# MondoBrickbridge.net
KiCad netlist of a schematic drawn in EAGLE
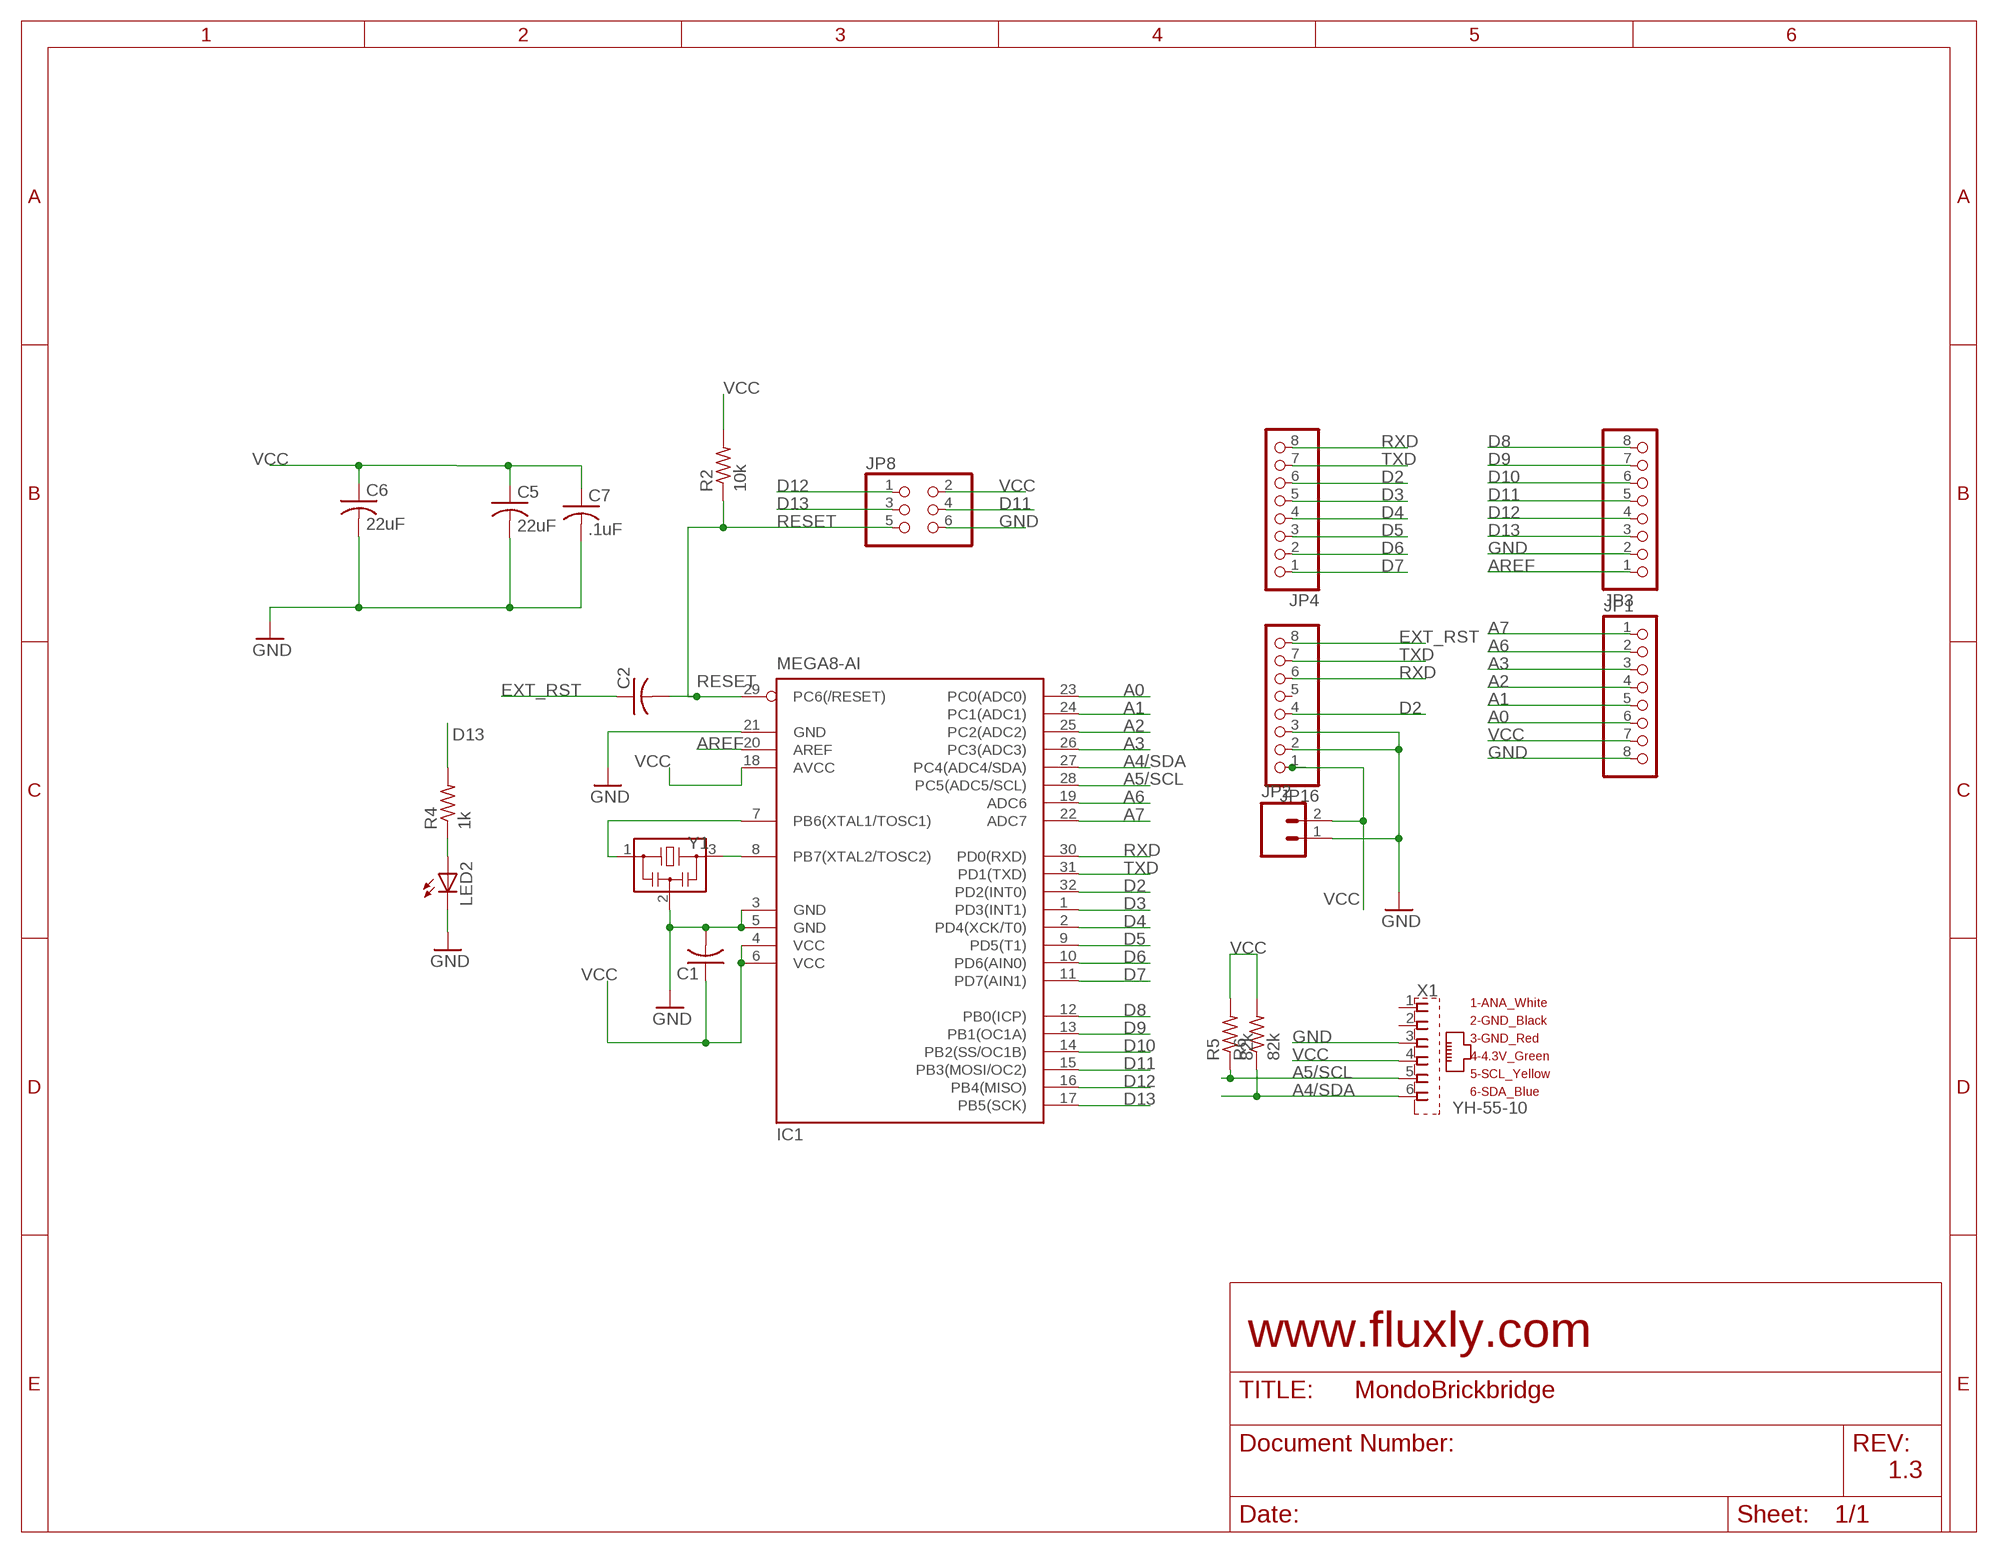
[diagram p0: schematic, sheet 1]

(export (version "E")
  (design (tool "Eeschema 10.0.6"))
  (components
    (comp (ref "C1")
      (value "C-USC0805K")
      (footprint "eagle-import:C0805K")
      (libsource (lib "eagle-import") (part "C-USC0805K"))
    )
    (comp (ref "C2")
      (value "C-USC0805K")
      (footprint "eagle-import:C0805K")
      (libsource (lib "eagle-import") (part "C-USC0805K"))
    )
    (comp (ref "C5")
      (value "22uF")
      (footprint "eagle-import:C1206K")
      (libsource (lib "eagle-import") (part "C-USC1206K"))
    )
    (comp (ref "C6")
      (value "22uF")
      (footprint "eagle-import:C1206K")
      (libsource (lib "eagle-import") (part "C-USC1206K"))
    )
    (comp (ref "C7")
      (value ".1uF")
      (footprint "eagle-import:C0805K")
      (libsource (lib "eagle-import") (part "C-USC0805K"))
    )
    (comp (ref "IC1")
      (value "MEGA8-AI")
      (footprint "eagle-import:TQFP32-08")
      (fields (field (name "MPN") "ATMEGA8-16AU"))
      (libsource (lib "eagle-import") (part "MEGA8-AI"))
    )
    (comp (ref "JP1")
      (value "PINHD-1X8BIG")
      (footprint "eagle-import:1X08-BIG")
      (libsource (lib "eagle-import") (part "PINHD-1X8BIG"))
    )
    (comp (ref "JP2")
      (value "M02PTH")
      (footprint "eagle-import:1X02")
      (libsource (lib "eagle-import") (part "M02PTH"))
    )
    (comp (ref "JP3")
      (value "PINHD-1X8BIG")
      (footprint "eagle-import:1X08-BIG")
      (libsource (lib "eagle-import") (part "PINHD-1X8BIG"))
    )
    (comp (ref "JP4")
      (value "PINHD-1X8BIG")
      (footprint "eagle-import:1X08-BIG")
      (libsource (lib "eagle-import") (part "PINHD-1X8BIG"))
    )
    (comp (ref "JP8")
      (value "PINHD-2X3")
      (footprint "eagle-import:2X03")
      (libsource (lib "eagle-import") (part "PINHD-2X3"))
    )
    (comp (ref "JP16")
      (value "PINHD-1X8BIG")
      (footprint "eagle-import:1X08-BIG")
      (libsource (lib "eagle-import") (part "PINHD-1X8BIG"))
    )
    (comp (ref "LED2")
      (value "LEDCHIPLED_1206")
      (footprint "eagle-import:CHIPLED_1206")
      (libsource (lib "eagle-import") (part "LEDCHIPLED_1206"))
    )
    (comp (ref "R2")
      (value "10k")
      (footprint "eagle-import:M0805")
      (libsource (lib "eagle-import") (part "R-US_M0805"))
    )
    (comp (ref "R4")
      (value "1k")
      (footprint "eagle-import:M0805")
      (libsource (lib "eagle-import") (part "R-US_M0805"))
    )
    (comp (ref "R5")
      (value "82k")
      (footprint "eagle-import:M0805")
      (libsource (lib "eagle-import") (part "R-US_M0805"))
    )
    (comp (ref "R6")
      (value "82k")
      (footprint "eagle-import:M0805")
      (libsource (lib "eagle-import") (part "R-US_M0805"))
    )
    (comp (ref "X1")
      (value "YH-55-10")
      (footprint "eagle-import:YH-55-10")
      (libsource (lib "eagle-import") (part "YH-55-10"))
    )
    (comp (ref "Y1")
      (value "RESONATOR")
      (footprint "eagle-import:EFOBM")
      (libsource (lib "eagle-import") (part "RESONATOR"))
    )
  )
  (nets
    (net (code "1") (name "/A0") (class "Default")
      (node (ref "IC1") (pin "23") (pinfunction "PC0(ADC0)_23") (pintype "bidirectional"))
      (node (ref "JP1") (pin "6") (pinfunction "6_6") (pintype "passive"))
    )
    (net (code "2") (name "/A1") (class "Default")
      (node (ref "IC1") (pin "24") (pinfunction "PC1(ADC1)_24") (pintype "bidirectional"))
      (node (ref "JP1") (pin "5") (pinfunction "5_5") (pintype "passive"))
    )
    (net (code "3") (name "/A2") (class "Default")
      (node (ref "IC1") (pin "25") (pinfunction "PC2(ADC2)_25") (pintype "bidirectional"))
      (node (ref "JP1") (pin "4") (pinfunction "4_4") (pintype "passive"))
    )
    (net (code "4") (name "/A3") (class "Default")
      (node (ref "IC1") (pin "26") (pinfunction "PC3(ADC3)_26") (pintype "bidirectional"))
      (node (ref "JP1") (pin "3") (pinfunction "3_3") (pintype "passive"))
    )
    (net (code "5") (name "/A4{slash}SDA") (class "Default")
      (node (ref "IC1") (pin "27") (pinfunction "PC4(ADC4/SDA)_27") (pintype "bidirectional"))
      (node (ref "R6") (pin "1") (pinfunction "1_1") (pintype "passive"))
      (node (ref "X1") (pin "6") (pinfunction "6_SDA_BLUE_6") (pintype "passive"))
    )
    (net (code "6") (name "/A5{slash}SCL") (class "Default")
      (node (ref "IC1") (pin "28") (pinfunction "PC5(ADC5/SCL)_28") (pintype "bidirectional"))
      (node (ref "R5") (pin "1") (pinfunction "1_1") (pintype "passive"))
      (node (ref "X1") (pin "5") (pinfunction "5_SCL_YELLOW_5") (pintype "passive"))
    )
    (net (code "7") (name "/A6") (class "Default")
      (node (ref "IC1") (pin "19") (pinfunction "ADC6_19") (pintype "bidirectional"))
      (node (ref "JP1") (pin "2") (pinfunction "2_2") (pintype "passive"))
    )
    (net (code "8") (name "/A7") (class "Default")
      (node (ref "IC1") (pin "22") (pinfunction "ADC7_22") (pintype "bidirectional"))
      (node (ref "JP1") (pin "1") (pinfunction "1_1") (pintype "passive"))
    )
    (net (code "9") (name "/AREF") (class "Default")
      (node (ref "IC1") (pin "20") (pinfunction "AREF_20") (pintype "passive"))
      (node (ref "JP3") (pin "1") (pinfunction "1_1") (pintype "passive"))
    )
    (net (code "10") (name "/D2") (class "Default")
      (node (ref "IC1") (pin "32") (pinfunction "PD2(INT0)_32") (pintype "bidirectional"))
      (node (ref "JP16") (pin "4") (pinfunction "4_4") (pintype "passive"))
      (node (ref "JP4") (pin "6") (pinfunction "6_6") (pintype "passive"))
    )
    (net (code "11") (name "/D3") (class "Default")
      (node (ref "IC1") (pin "1") (pinfunction "PD3(INT1)_1") (pintype "bidirectional"))
      (node (ref "JP4") (pin "5") (pinfunction "5_5") (pintype "passive"))
    )
    (net (code "12") (name "/D4") (class "Default")
      (node (ref "IC1") (pin "2") (pinfunction "PD4(XCK/T0)_2") (pintype "bidirectional"))
      (node (ref "JP4") (pin "4") (pinfunction "4_4") (pintype "passive"))
    )
    (net (code "13") (name "/D5") (class "Default")
      (node (ref "IC1") (pin "9") (pinfunction "PD5(T1)_9") (pintype "bidirectional"))
      (node (ref "JP4") (pin "3") (pinfunction "3_3") (pintype "passive"))
    )
    (net (code "14") (name "/D6") (class "Default")
      (node (ref "IC1") (pin "10") (pinfunction "PD6(AIN0)_10") (pintype "bidirectional"))
      (node (ref "JP4") (pin "2") (pinfunction "2_2") (pintype "passive"))
    )
    (net (code "15") (name "/D7") (class "Default")
      (node (ref "IC1") (pin "11") (pinfunction "PD7(AIN1)_11") (pintype "bidirectional"))
      (node (ref "JP4") (pin "1") (pinfunction "1_1") (pintype "passive"))
    )
    (net (code "16") (name "/D8") (class "Default")
      (node (ref "IC1") (pin "12") (pinfunction "PB0(ICP)_12") (pintype "bidirectional"))
      (node (ref "JP3") (pin "8") (pinfunction "8_8") (pintype "passive"))
    )
    (net (code "17") (name "/D9") (class "Default")
      (node (ref "IC1") (pin "13") (pinfunction "PB1(OC1A)_13") (pintype "bidirectional"))
      (node (ref "JP3") (pin "7") (pinfunction "7_7") (pintype "passive"))
    )
    (net (code "18") (name "/D10") (class "Default")
      (node (ref "IC1") (pin "14") (pinfunction "PB2(SS/OC1B)_14") (pintype "bidirectional"))
      (node (ref "JP3") (pin "6") (pinfunction "6_6") (pintype "passive"))
    )
    (net (code "19") (name "/D11") (class "Default")
      (node (ref "IC1") (pin "15") (pinfunction "PB3(MOSI/OC2)_15") (pintype "bidirectional"))
      (node (ref "JP3") (pin "5") (pinfunction "5_5") (pintype "passive"))
      (node (ref "JP8") (pin "4") (pinfunction "4_4") (pintype "passive"))
    )
    (net (code "20") (name "/D12") (class "Default")
      (node (ref "IC1") (pin "16") (pinfunction "PB4(MISO)_16") (pintype "bidirectional"))
      (node (ref "JP3") (pin "4") (pinfunction "4_4") (pintype "passive"))
      (node (ref "JP8") (pin "1") (pinfunction "1_1") (pintype "passive"))
    )
    (net (code "21") (name "/D13") (class "Default")
      (node (ref "IC1") (pin "17") (pinfunction "PB5(SCK)_17") (pintype "bidirectional"))
      (node (ref "JP3") (pin "3") (pinfunction "3_3") (pintype "passive"))
      (node (ref "JP8") (pin "3") (pinfunction "3_3") (pintype "passive"))
      (node (ref "R4") (pin "2") (pinfunction "2_2") (pintype "passive"))
    )
    (net (code "22") (name "/EXT_RST") (class "Default")
      (node (ref "C2") (pin "1") (pinfunction "1_1") (pintype "passive"))
      (node (ref "JP16") (pin "8") (pinfunction "8_8") (pintype "passive"))
    )
    (net (code "23") (name "/RESET") (class "Default")
      (node (ref "C2") (pin "2") (pinfunction "2_2") (pintype "passive"))
      (node (ref "IC1") (pin "29") (pinfunction "PC6(/RESET)_29") (pintype "bidirectional"))
      (node (ref "JP8") (pin "5") (pinfunction "5_5") (pintype "passive"))
      (node (ref "R2") (pin "1") (pinfunction "1_1") (pintype "passive"))
    )
    (net (code "24") (name "/RXD") (class "Default")
      (node (ref "IC1") (pin "30") (pinfunction "PD0(RXD)_30") (pintype "bidirectional"))
      (node (ref "JP16") (pin "6") (pinfunction "6_6") (pintype "passive"))
      (node (ref "JP4") (pin "8") (pinfunction "8_8") (pintype "passive"))
    )
    (net (code "25") (name "/TXD") (class "Default")
      (node (ref "IC1") (pin "31") (pinfunction "PD1(TXD)_31") (pintype "bidirectional"))
      (node (ref "JP16") (pin "7") (pinfunction "7_7") (pintype "passive"))
      (node (ref "JP4") (pin "7") (pinfunction "7_7") (pintype "passive"))
    )
    (net (code "26") (name "/VCC") (class "Default")
      (node (ref "C1") (pin "1") (pinfunction "1_1") (pintype "passive"))
      (node (ref "C5") (pin "1") (pinfunction "1_1") (pintype "passive"))
      (node (ref "C6") (pin "1") (pinfunction "1_1") (pintype "passive"))
      (node (ref "C7") (pin "1") (pinfunction "1_1") (pintype "passive"))
      (node (ref "IC1") (pin "18") (pinfunction "AVCC_18") (pintype "power_in"))
      (node (ref "IC1") (pin "4") (pinfunction "VCC_4") (pintype "power_in"))
      (node (ref "IC1") (pin "6") (pinfunction "VCC_6") (pintype "power_in"))
      (node (ref "JP1") (pin "7") (pinfunction "7_7") (pintype "passive"))
      (node (ref "JP16") (pin "1") (pinfunction "1_1") (pintype "passive"))
      (node (ref "JP2") (pin "2") (pinfunction "2_2") (pintype "passive"))
      (node (ref "JP8") (pin "2") (pinfunction "2_2") (pintype "passive"))
      (node (ref "R2") (pin "2") (pinfunction "2_2") (pintype "passive"))
      (node (ref "R5") (pin "2") (pinfunction "2_2") (pintype "passive"))
      (node (ref "R6") (pin "2") (pinfunction "2_2") (pintype "passive"))
      (node (ref "X1") (pin "4") (pinfunction "4_4.3V_GREEN_4") (pintype "passive"))
    )
    (net (code "27") (name "GND") (class "Default")
      (node (ref "C1") (pin "2") (pinfunction "2_2") (pintype "passive"))
      (node (ref "C5") (pin "2") (pinfunction "2_2") (pintype "passive"))
      (node (ref "C6") (pin "2") (pinfunction "2_2") (pintype "passive"))
      (node (ref "C7") (pin "2") (pinfunction "2_2") (pintype "passive"))
      (node (ref "IC1") (pin "21") (pinfunction "GND_21") (pintype "power_in"))
      (node (ref "IC1") (pin "3") (pinfunction "GND_3") (pintype "power_in"))
      (node (ref "IC1") (pin "5") (pinfunction "GND_5") (pintype "power_in"))
      (node (ref "JP1") (pin "8") (pinfunction "8_8") (pintype "passive"))
      (node (ref "JP16") (pin "2") (pinfunction "2_2") (pintype "passive"))
      (node (ref "JP16") (pin "3") (pinfunction "3_3") (pintype "passive"))
      (node (ref "JP2") (pin "1") (pinfunction "1_1") (pintype "passive"))
      (node (ref "JP3") (pin "2") (pinfunction "2_2") (pintype "passive"))
      (node (ref "JP8") (pin "6") (pinfunction "6_6") (pintype "passive"))
      (node (ref "LED2") (pin "C") (pinfunction "C_C") (pintype "passive"))
      (node (ref "X1") (pin "3") (pinfunction "3_GND_RED_3") (pintype "passive"))
      (node (ref "Y1") (pin "2") (pinfunction "2_2") (pintype "passive"))
    )
    (net (code "28") (name "Net-(IC1-PB6(XTAL1{slash}TOSC1))") (class "Default")
      (node (ref "IC1") (pin "7") (pinfunction "PB6(XTAL1/TOSC1)_7") (pintype "bidirectional"))
      (node (ref "Y1") (pin "1") (pinfunction "1_1") (pintype "passive"))
    )
    (net (code "29") (name "Net-(IC1-PB7(XTAL2{slash}TOSC2))") (class "Default")
      (node (ref "IC1") (pin "8") (pinfunction "PB7(XTAL2/TOSC2)_8") (pintype "bidirectional"))
      (node (ref "Y1") (pin "3") (pinfunction "3_3") (pintype "passive"))
    )
    (net (code "30") (name "Net-(LED2-PadA)") (class "Default")
      (node (ref "LED2") (pin "A") (pinfunction "A_A") (pintype "passive"))
      (node (ref "R4") (pin "1") (pinfunction "1_1") (pintype "passive"))
    )
    (net (code "31") (name "unconnected-(JP16-Pad5)") (class "Default")
      (node (ref "JP16") (pin "5") (pinfunction "5_5") (pintype "passive"))
    )
    (net (code "32") (name "unconnected-(X1-1_ANA_WHITE-Pad1)") (class "Default")
      (node (ref "X1") (pin "1") (pinfunction "1_ANA_WHITE_1") (pintype "passive"))
    )
    (net (code "33") (name "unconnected-(X1-2_GND_BLACK-Pad2)") (class "Default")
      (node (ref "X1") (pin "2") (pinfunction "2_GND_BLACK_2") (pintype "passive"))
    )
  )
)
